# ver3_0_VinSeparat.net
KiCad netlist of a schematic drawn in EAGLE
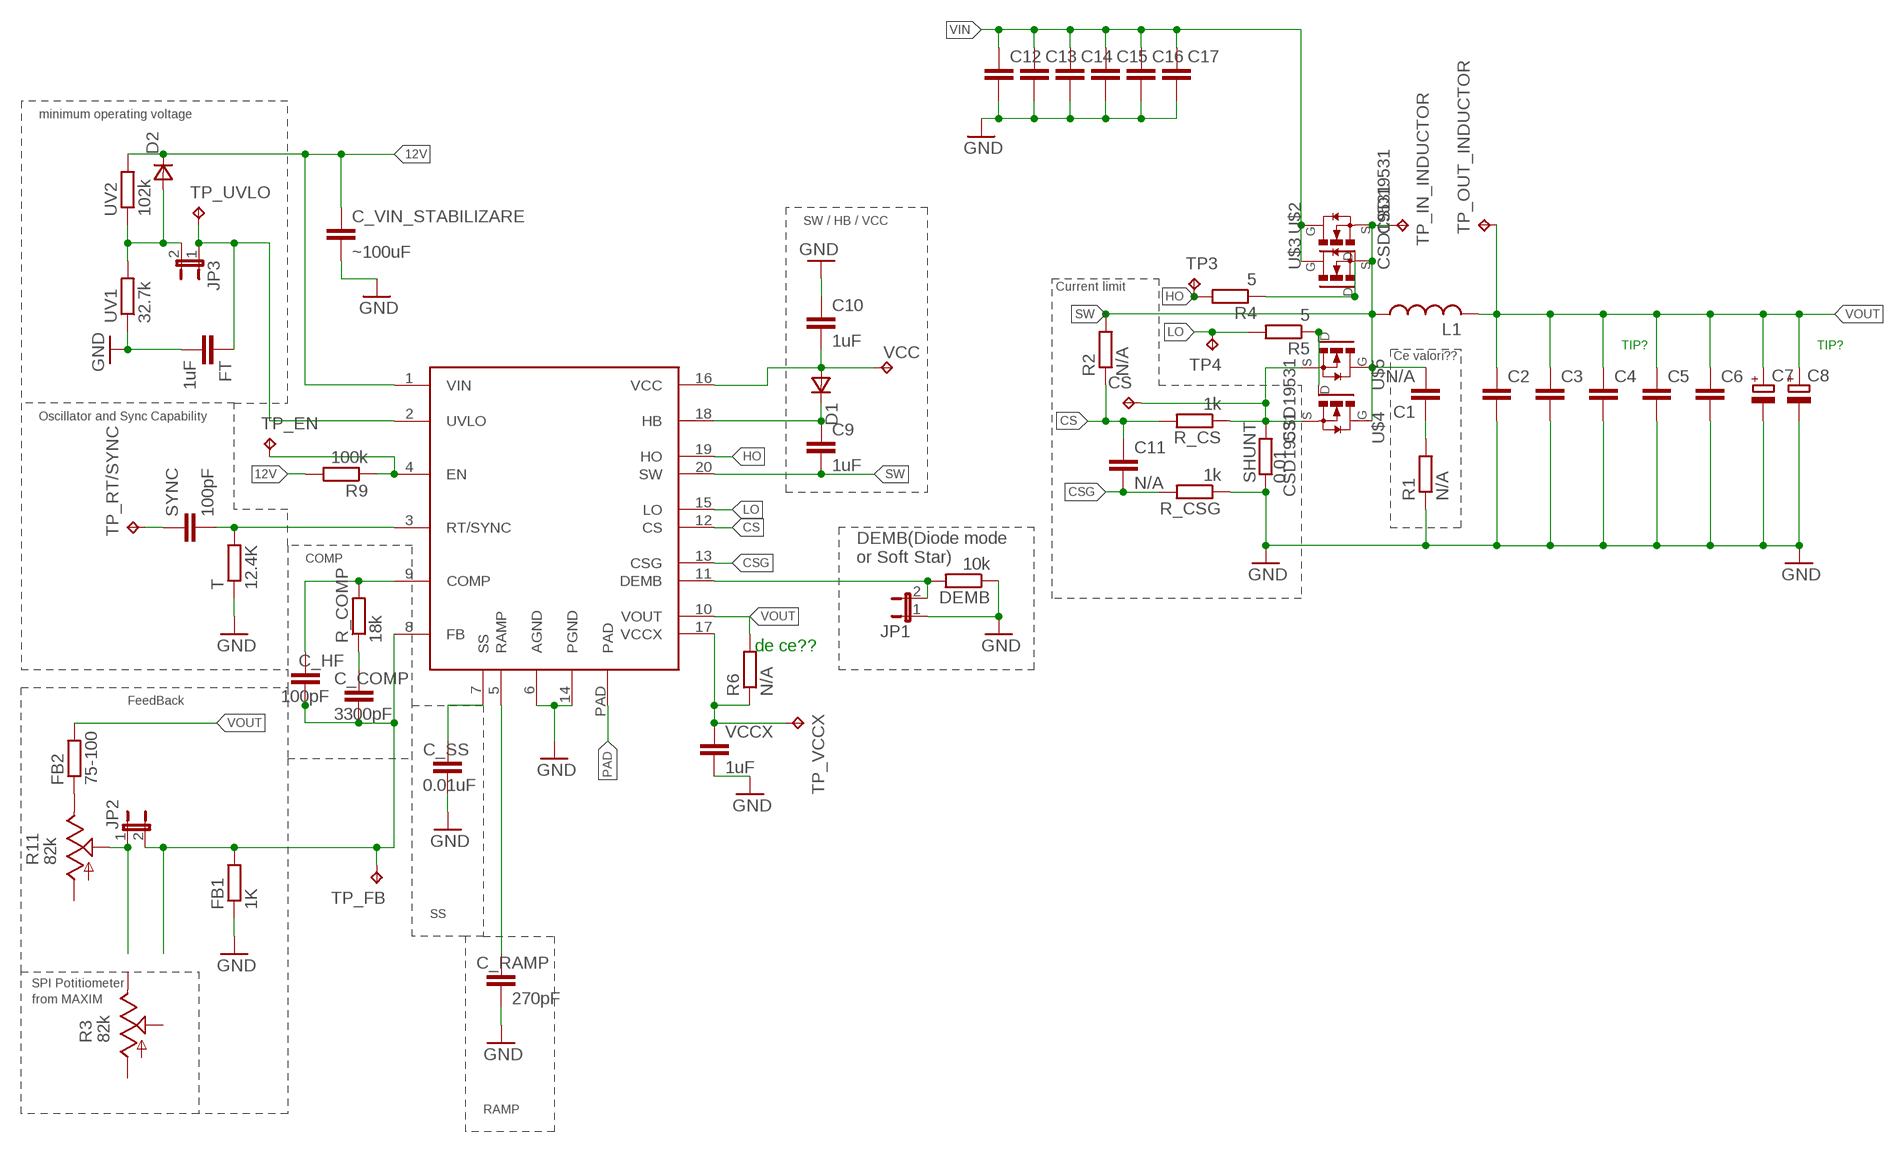
[diagram p0: schematic, sheet 1]

(export (version "E")
  (design (tool "Eeschema 10.0.6"))
  (components
    (comp (ref "C1")
      (value "N/A")
      (footprint "eagle-import:C0805K")
      (libsource (lib "eagle-import") (part "resistor_C-EUC0805K"))
    )
    (comp (ref "C2")
      (value "C-EUC1812")
      (footprint "eagle-import:C1812")
      (libsource (lib "eagle-import") (part "C-EUC1812"))
    )
    (comp (ref "C3")
      (value "C-EUC1812")
      (footprint "eagle-import:C1812")
      (libsource (lib "eagle-import") (part "C-EUC1812"))
    )
    (comp (ref "C4")
      (value "C-EUC1812")
      (footprint "eagle-import:C1812")
      (libsource (lib "eagle-import") (part "C-EUC1812"))
    )
    (comp (ref "C5")
      (value "C-EUC1812")
      (footprint "eagle-import:C1812")
      (libsource (lib "eagle-import") (part "C-EUC1812"))
    )
    (comp (ref "C6")
      (value "C-EUC1812")
      (footprint "eagle-import:C1812")
      (libsource (lib "eagle-import") (part "C-EUC1812"))
    )
    (comp (ref "C7")
      (value "CPOL-EU153CLV-1012")
      (footprint "eagle-import:153CLV-1012")
      (libsource (lib "eagle-import") (part "CPOL-EU153CLV-1012"))
    )
    (comp (ref "C8")
      (value "CPOL-EU153CLV-1012")
      (footprint "eagle-import:153CLV-1012")
      (libsource (lib "eagle-import") (part "CPOL-EU153CLV-1012"))
    )
    (comp (ref "C9")
      (value "1uF")
      (footprint "eagle-import:C0805K")
      (libsource (lib "eagle-import") (part "resistor_C-EUC0805K"))
    )
    (comp (ref "C10")
      (value "1uF")
      (footprint "eagle-import:C0805K")
      (libsource (lib "eagle-import") (part "resistor_C-EUC0805K"))
    )
    (comp (ref "C11")
      (value "N/A")
      (footprint "eagle-import:C0805K")
      (libsource (lib "eagle-import") (part "resistor_C-EUC0805K"))
    )
    (comp (ref "C12")
      (value "C-EUC1812K")
      (footprint "eagle-import:C1812K")
      (libsource (lib "eagle-import") (part "C-EUC1812K"))
    )
    (comp (ref "C13")
      (value "C-EUC1812K")
      (footprint "eagle-import:C1812K")
      (libsource (lib "eagle-import") (part "C-EUC1812K"))
    )
    (comp (ref "C14")
      (value "C-EUC1812K")
      (footprint "eagle-import:C1812K")
      (libsource (lib "eagle-import") (part "C-EUC1812K"))
    )
    (comp (ref "C15")
      (value "C-EUC1812K")
      (footprint "eagle-import:C1812K")
      (libsource (lib "eagle-import") (part "C-EUC1812K"))
    )
    (comp (ref "C16")
      (value "C-EUC1812K")
      (footprint "eagle-import:C1812K")
      (libsource (lib "eagle-import") (part "C-EUC1812K"))
    )
    (comp (ref "C17")
      (value "C-EUC1812K")
      (footprint "eagle-import:C1812K")
      (libsource (lib "eagle-import") (part "C-EUC1812K"))
    )
    (comp (ref "CS")
      (value "TPPAD1-20")
      (footprint "eagle-import:P1-20")
      (libsource (lib "eagle-import") (part "TPPAD1-20"))
    )
    (comp (ref "C_COMP")
      (value "3300pF")
      (footprint "eagle-import:C0805K")
      (libsource (lib "eagle-import") (part "resistor_C-EUC0805K"))
    )
    (comp (ref "C_HF")
      (value "100pF")
      (footprint "eagle-import:C0805K")
      (libsource (lib "eagle-import") (part "resistor_C-EUC0805K"))
    )
    (comp (ref "C_RAMP")
      (value "270pF")
      (footprint "eagle-import:C0805K")
      (libsource (lib "eagle-import") (part "resistor_C-EUC0805K"))
    )
    (comp (ref "C_SS")
      (value "0.01uF")
      (footprint "eagle-import:C0805K")
      (libsource (lib "eagle-import") (part "resistor_C-EUC0805K"))
    )
    (comp (ref "C_VIN_STABILIZARE")
      (value "~100uF")
      (footprint "eagle-import:C0805K")
      (libsource (lib "eagle-import") (part "resistor_C-EUC0805K"))
    )
    (comp (ref "D1")
      (value "DSOT23")
      (footprint "eagle-import:SOT-23")
      (fields (field (name "MPN") "CDSOT23-T03"))
      (libsource (lib "eagle-import") (part "DSOT23"))
    )
    (comp (ref "D2")
      (value "DSOT23")
      (footprint "eagle-import:SOT-23")
      (fields (field (name "MPN") "CDSOT23-T03"))
      (libsource (lib "eagle-import") (part "DSOT23"))
    )
    (comp (ref "DEMB")
      (value "10k")
      (footprint "eagle-import:R0603")
      (libsource (lib "eagle-import") (part "R-EU_R0603"))
    )
    (comp (ref "FB1")
      (value "1K")
      (footprint "eagle-import:R0603")
      (libsource (lib "eagle-import") (part "R-EU_R0603"))
    )
    (comp (ref "FB2")
      (value "75-100")
      (footprint "eagle-import:R0603")
      (libsource (lib "eagle-import") (part "R-EU_R0603"))
    )
    (comp (ref "FT")
      (value "1uF")
      (footprint "eagle-import:C1812K")
      (libsource (lib "eagle-import") (part "C-EUC1812K"))
    )
    (comp (ref "JP1")
      (value "JP1E")
      (footprint "eagle-import:JP1")
      (libsource (lib "eagle-import") (part "JP1E"))
    )
    (comp (ref "JP2")
      (value "JP1E")
      (footprint "eagle-import:JP1")
      (libsource (lib "eagle-import") (part "JP1E"))
    )
    (comp (ref "JP3")
      (value "JP1E")
      (footprint "eagle-import:JP1")
      (libsource (lib "eagle-import") (part "JP1E"))
    )
    (comp (ref "L1")
      (value "L-USTJ8-U2")
      (footprint "eagle-import:TJ8-U2")
      (libsource (lib "eagle-import") (part "L-USTJ8-U2"))
    )
    (comp (ref "R1")
      (value "N/A")
      (footprint "eagle-import:M1206")
      (libsource (lib "eagle-import") (part "resistor_R-EU_M1206"))
    )
    (comp (ref "R2")
      (value "N/A")
      (footprint "eagle-import:R0603")
      (libsource (lib "eagle-import") (part "R-EU_R0603"))
    )
    (comp (ref "R3")
      (value "82k")
      (footprint "eagle-import:B64Y")
      (libsource (lib "eagle-import") (part "TRIM_US-B64Y"))
    )
    (comp (ref "R4")
      (value "5")
      (footprint "eagle-import:M1206")
      (libsource (lib "eagle-import") (part "resistor_R-EU_M1206"))
    )
    (comp (ref "R5")
      (value "5")
      (footprint "eagle-import:M1206")
      (libsource (lib "eagle-import") (part "resistor_R-EU_M1206"))
    )
    (comp (ref "R6")
      (value "N/A")
      (footprint "eagle-import:R0603")
      (libsource (lib "eagle-import") (part "R-EU_R0603"))
    )
    (comp (ref "R9")
      (value "100k")
      (footprint "eagle-import:R0603")
      (libsource (lib "eagle-import") (part "R-EU_R0603"))
    )
    (comp (ref "R11")
      (value "82k")
      (footprint "eagle-import:B64Y")
      (libsource (lib "eagle-import") (part "TRIM_US-B64Y"))
    )
    (comp (ref "R_COMP")
      (value "18k")
      (footprint "eagle-import:R0603")
      (libsource (lib "eagle-import") (part "R-EU_R0603"))
    )
    (comp (ref "R_CS")
      (value "1k")
      (footprint "eagle-import:R0603")
      (libsource (lib "eagle-import") (part "R-EU_R0603"))
    )
    (comp (ref "R_CSG")
      (value "1k")
      (footprint "eagle-import:R0603")
      (libsource (lib "eagle-import") (part "R-EU_R0603"))
    )
    (comp (ref "SHUNT")
      (value "0.01")
      (footprint "eagle-import:SMR-0")
      (libsource (lib "eagle-import") (part "SMR-0"))
    )
    (comp (ref "SYNC")
      (value "100pF")
      (footprint "eagle-import:C0805K")
      (libsource (lib "eagle-import") (part "resistor_C-EUC0805K"))
    )
    (comp (ref "T")
      (value "12.4K")
      (footprint "eagle-import:R0603")
      (libsource (lib "eagle-import") (part "R-EU_R0603"))
    )
    (comp (ref "TP3")
      (value "TPPAD1-20")
      (footprint "eagle-import:P1-20")
      (libsource (lib "eagle-import") (part "TPPAD1-20"))
    )
    (comp (ref "TP4")
      (value "TPPAD1-20")
      (footprint "eagle-import:P1-20")
      (libsource (lib "eagle-import") (part "TPPAD1-20"))
    )
    (comp (ref "TP_EN")
      (value "TPPAD1-20")
      (footprint "eagle-import:P1-20")
      (libsource (lib "eagle-import") (part "TPPAD1-20"))
    )
    (comp (ref "TP_FB")
      (value "TPPAD1-20")
      (footprint "eagle-import:P1-20")
      (libsource (lib "eagle-import") (part "TPPAD1-20"))
    )
    (comp (ref "TP_IN_INDUCTOR")
      (value "TPPAD1-20")
      (footprint "eagle-import:P1-20")
      (libsource (lib "eagle-import") (part "TPPAD1-20"))
    )
    (comp (ref "TP_OUT_INDUCTOR")
      (value "TPPAD1-20")
      (footprint "eagle-import:P1-20")
      (libsource (lib "eagle-import") (part "TPPAD1-20"))
    )
    (comp (ref "TP_RT/SYNC")
      (value "TPPAD1-20")
      (footprint "eagle-import:P1-20")
      (libsource (lib "eagle-import") (part "TPPAD1-20"))
    )
    (comp (ref "TP_UVLO")
      (value "TPPAD1-20")
      (footprint "eagle-import:P1-20")
      (libsource (lib "eagle-import") (part "TPPAD1-20"))
    )
    (comp (ref "TP_VCCX")
      (value "TPPAD1-20")
      (footprint "eagle-import:P1-20")
      (libsource (lib "eagle-import") (part "TPPAD1-20"))
    )
    (comp (ref "U$1")
      (value "LM5116")
      (footprint "eagle-import:TSSOP20")
      (libsource (lib "eagle-import") (part "LM5116"))
    )
    (comp (ref "U$2")
      (value "CSD19531")
      (footprint "eagle-import:TO220H")
      (libsource (lib "eagle-import") (part "CSD19531"))
    )
    (comp (ref "U$3")
      (value "CSD19531")
      (footprint "eagle-import:TO220H")
      (libsource (lib "eagle-import") (part "CSD19531"))
    )
    (comp (ref "U$4")
      (value "CSD19531")
      (footprint "eagle-import:TO220H")
      (libsource (lib "eagle-import") (part "CSD19531"))
    )
    (comp (ref "U$5")
      (value "CSD19531")
      (footprint "eagle-import:TO220H")
      (libsource (lib "eagle-import") (part "CSD19531"))
    )
    (comp (ref "UV1")
      (value "32.7k")
      (footprint "eagle-import:R0603")
      (libsource (lib "eagle-import") (part "R-EU_R0603"))
    )
    (comp (ref "UV2")
      (value "102k")
      (footprint "eagle-import:R0603")
      (libsource (lib "eagle-import") (part "R-EU_R0603"))
    )
    (comp (ref "VCC")
      (value "TPPAD1-20")
      (footprint "eagle-import:P1-20")
      (libsource (lib "eagle-import") (part "TPPAD1-20"))
    )
    (comp (ref "VCCX")
      (value "1uF")
      (footprint "eagle-import:C0805K")
      (libsource (lib "eagle-import") (part "resistor_C-EUC0805K"))
    )
  )
  (nets
    (net (code "1") (name "12V") (class "Default")
      (node (ref "C_VIN_STABILIZARE") (pin "1") (pinfunction "1_1") (pintype "passive"))
      (node (ref "D2") (pin "1") (pinfunction "C_1") (pintype "passive"))
      (node (ref "R9") (pin "2") (pinfunction "2_2") (pintype "passive"))
      (node (ref "U$1") (pin "1") (pinfunction "VIN_1") (pintype "power_in"))
      (node (ref "UV2") (pin "2") (pinfunction "2_2") (pintype "passive"))
    )
    (net (code "2") (name "CS") (class "Default")
      (node (ref "C11") (pin "1") (pinfunction "1_1") (pintype "passive"))
      (node (ref "R2") (pin "1") (pinfunction "1_1") (pintype "passive"))
      (node (ref "R_CS") (pin "2") (pinfunction "2_2") (pintype "passive"))
      (node (ref "U$1") (pin "12") (pinfunction "CS_12") (pintype "bidirectional"))
    )
    (net (code "3") (name "CSG") (class "Default")
      (node (ref "C11") (pin "2") (pinfunction "2_2") (pintype "passive"))
      (node (ref "R_CSG") (pin "2") (pinfunction "2_2") (pintype "passive"))
      (node (ref "U$1") (pin "13") (pinfunction "CSG_13") (pintype "bidirectional"))
    )
    (net (code "4") (name "GND") (class "Default")
      (node (ref "C10") (pin "1") (pinfunction "1_1") (pintype "passive"))
      (node (ref "C12") (pin "2") (pinfunction "2_2") (pintype "passive"))
      (node (ref "C13") (pin "2") (pinfunction "2_2") (pintype "passive"))
      (node (ref "C14") (pin "2") (pinfunction "2_2") (pintype "passive"))
      (node (ref "C15") (pin "2") (pinfunction "2_2") (pintype "passive"))
      (node (ref "C16") (pin "2") (pinfunction "2_2") (pintype "passive"))
      (node (ref "C17") (pin "2") (pinfunction "2_2") (pintype "passive"))
      (node (ref "C2") (pin "2") (pinfunction "2_2") (pintype "passive"))
      (node (ref "C3") (pin "2") (pinfunction "2_2") (pintype "passive"))
      (node (ref "C4") (pin "2") (pinfunction "2_2") (pintype "passive"))
      (node (ref "C5") (pin "2") (pinfunction "2_2") (pintype "passive"))
      (node (ref "C6") (pin "2") (pinfunction "2_2") (pintype "passive"))
      (node (ref "C7") (pin "-") (pinfunction "-_-") (pintype "passive"))
      (node (ref "C8") (pin "-") (pinfunction "-_-") (pintype "passive"))
      (node (ref "C_RAMP") (pin "2") (pinfunction "2_2") (pintype "passive"))
      (node (ref "C_SS") (pin "2") (pinfunction "2_2") (pintype "passive"))
      (node (ref "C_VIN_STABILIZARE") (pin "2") (pinfunction "2_2") (pintype "passive"))
      (node (ref "DEMB") (pin "1") (pinfunction "1_1") (pintype "passive"))
      (node (ref "FB1") (pin "1") (pinfunction "1_1") (pintype "passive"))
      (node (ref "FT") (pin "2") (pinfunction "2_2") (pintype "passive"))
      (node (ref "JP1") (pin "1") (pinfunction "1_1") (pintype "passive"))
      (node (ref "R1") (pin "1") (pinfunction "1_1") (pintype "passive"))
      (node (ref "R_CSG") (pin "1") (pinfunction "1_1") (pintype "passive"))
      (node (ref "SHUNT") (pin "2") (pinfunction "2_2") (pintype "passive"))
      (node (ref "T") (pin "1") (pinfunction "1_1") (pintype "passive"))
      (node (ref "U$1") (pin "14") (pinfunction "PGND_14") (pintype "bidirectional"))
      (node (ref "U$1") (pin "6") (pinfunction "AGND_6") (pintype "bidirectional"))
      (node (ref "UV1") (pin "1") (pinfunction "1_1") (pintype "passive"))
      (node (ref "VCCX") (pin "2") (pinfunction "2_2") (pintype "passive"))
    )
    (net (code "5") (name "HO") (class "Default")
      (node (ref "R4") (pin "2") (pinfunction "2_2") (pintype "passive"))
      (node (ref "TP3") (pin "TP") (pinfunction "TP_TP") (pintype "input"))
      (node (ref "U$1") (pin "19") (pinfunction "HO_19") (pintype "bidirectional"))
    )
    (net (code "6") (name "LO") (class "Default")
      (node (ref "R5") (pin "2") (pinfunction "2_2") (pintype "passive"))
      (node (ref "TP4") (pin "TP") (pinfunction "TP_TP") (pintype "input"))
      (node (ref "U$1") (pin "15") (pinfunction "LO_15") (pintype "bidirectional"))
    )
    (net (code "7") (name "Net-(C1-Pad1)") (class "Default")
      (node (ref "C1") (pin "1") (pinfunction "1_1") (pintype "passive"))
      (node (ref "R1") (pin "2") (pinfunction "2_2") (pintype "passive"))
    )
    (net (code "8") (name "Net-(C_COMP-Pad1)") (class "Default")
      (node (ref "C_COMP") (pin "1") (pinfunction "1_1") (pintype "passive"))
      (node (ref "R_COMP") (pin "1") (pinfunction "1_1") (pintype "passive"))
    )
    (net (code "9") (name "Net-(D1-A)") (class "Default")
      (node (ref "C10") (pin "2") (pinfunction "2_2") (pintype "passive"))
      (node (ref "D1") (pin "3") (pinfunction "A_3") (pintype "passive"))
      (node (ref "U$1") (pin "16") (pinfunction "VCC_16") (pintype "bidirectional"))
      (node (ref "VCC") (pin "TP") (pinfunction "TP_TP") (pintype "input"))
    )
    (net (code "10") (name "Net-(D1-C)") (class "Default")
      (node (ref "C9") (pin "1") (pinfunction "1_1") (pintype "passive"))
      (node (ref "D1") (pin "1") (pinfunction "C_1") (pintype "passive"))
      (node (ref "U$1") (pin "18") (pinfunction "HB_18") (pintype "bidirectional"))
    )
    (net (code "11") (name "Net-(D2-A)") (class "Default")
      (node (ref "D2") (pin "3") (pinfunction "A_3") (pintype "passive"))
      (node (ref "JP3") (pin "2") (pinfunction "2_2") (pintype "passive"))
      (node (ref "UV1") (pin "2") (pinfunction "2_2") (pintype "passive"))
      (node (ref "UV2") (pin "1") (pinfunction "1_1") (pintype "passive"))
    )
    (net (code "12") (name "Net-(FB2-Pad1)") (class "Default")
      (node (ref "FB2") (pin "1") (pinfunction "1_1") (pintype "passive"))
      (node (ref "R11") (pin "E") (pinfunction "E_E") (pintype "passive"))
    )
    (net (code "13") (name "Net-(JP2-Pad1)") (class "Default")
      (node (ref "JP2") (pin "1") (pinfunction "1_1") (pintype "passive"))
      (node (ref "R11") (pin "S") (pinfunction "S_S") (pintype "passive"))
    )
    (net (code "14") (name "Net-(SYNC-Pad1)") (class "Default")
      (node (ref "SYNC") (pin "1") (pinfunction "1_1") (pintype "passive"))
      (node (ref "TP_RT/SYNC") (pin "TP") (pinfunction "TP_TP") (pintype "input"))
    )
    (net (code "15") (name "Net-(U$1-COMP)") (class "Default")
      (node (ref "C_HF") (pin "1") (pinfunction "1_1") (pintype "passive"))
      (node (ref "R_COMP") (pin "2") (pinfunction "2_2") (pintype "passive"))
      (node (ref "U$1") (pin "9") (pinfunction "COMP_9") (pintype "bidirectional"))
    )
    (net (code "16") (name "Net-(U$1-DEMB)") (class "Default")
      (node (ref "DEMB") (pin "2") (pinfunction "2_2") (pintype "passive"))
      (node (ref "JP1") (pin "2") (pinfunction "2_2") (pintype "passive"))
      (node (ref "U$1") (pin "11") (pinfunction "DEMB_11") (pintype "bidirectional"))
    )
    (net (code "17") (name "Net-(U$1-EN)") (class "Default")
      (node (ref "R9") (pin "1") (pinfunction "1_1") (pintype "passive"))
      (node (ref "TP_EN") (pin "TP") (pinfunction "TP_TP") (pintype "input"))
      (node (ref "U$1") (pin "4") (pinfunction "EN_4") (pintype "bidirectional"))
    )
    (net (code "18") (name "Net-(U$1-FB)") (class "Default")
      (node (ref "C_COMP") (pin "2") (pinfunction "2_2") (pintype "passive"))
      (node (ref "C_HF") (pin "2") (pinfunction "2_2") (pintype "passive"))
      (node (ref "FB1") (pin "2") (pinfunction "2_2") (pintype "passive"))
      (node (ref "JP2") (pin "2") (pinfunction "2_2") (pintype "passive"))
      (node (ref "TP_FB") (pin "TP") (pinfunction "TP_TP") (pintype "input"))
      (node (ref "U$1") (pin "8") (pinfunction "FB_8") (pintype "bidirectional"))
    )
    (net (code "19") (name "Net-(U$1-RAMP)") (class "Default")
      (node (ref "C_RAMP") (pin "1") (pinfunction "1_1") (pintype "passive"))
      (node (ref "U$1") (pin "5") (pinfunction "RAMP_5") (pintype "bidirectional"))
    )
    (net (code "20") (name "Net-(U$1-RT{slash}SYNC)") (class "Default")
      (node (ref "SYNC") (pin "2") (pinfunction "2_2") (pintype "passive"))
      (node (ref "T") (pin "2") (pinfunction "2_2") (pintype "passive"))
      (node (ref "U$1") (pin "3") (pinfunction "RT/SYNC_3") (pintype "bidirectional"))
    )
    (net (code "21") (name "Net-(U$1-SS)") (class "Default")
      (node (ref "C_SS") (pin "1") (pinfunction "1_1") (pintype "passive"))
      (node (ref "U$1") (pin "7") (pinfunction "SS_7") (pintype "bidirectional"))
    )
    (net (code "22") (name "Net-(U$1-UVLO)") (class "Default")
      (node (ref "FT") (pin "1") (pinfunction "1_1") (pintype "passive"))
      (node (ref "JP3") (pin "1") (pinfunction "1_1") (pintype "passive"))
      (node (ref "TP_UVLO") (pin "TP") (pinfunction "TP_TP") (pintype "input"))
      (node (ref "U$1") (pin "2") (pinfunction "UVLO_2") (pintype "bidirectional"))
    )
    (net (code "23") (name "Net-(U$1-VCCX)") (class "Default")
      (node (ref "R6") (pin "1") (pinfunction "1_1") (pintype "passive"))
      (node (ref "TP_VCCX") (pin "TP") (pinfunction "TP_TP") (pintype "input"))
      (node (ref "U$1") (pin "17") (pinfunction "VCCX_17") (pintype "bidirectional"))
      (node (ref "VCCX") (pin "1") (pinfunction "1_1") (pintype "passive"))
    )
    (net (code "24") (name "Net-(U$2-G)") (class "Default")
      (node (ref "R4") (pin "1") (pinfunction "1_1") (pintype "passive"))
      (node (ref "U$2") (pin "1") (pinfunction "G_1") (pintype "passive"))
      (node (ref "U$3") (pin "1") (pinfunction "G_1") (pintype "passive"))
    )
    (net (code "25") (name "Net-(U$4-G)") (class "Default")
      (node (ref "R5") (pin "1") (pinfunction "1_1") (pintype "passive"))
      (node (ref "U$4") (pin "1") (pinfunction "G_1") (pintype "passive"))
      (node (ref "U$5") (pin "1") (pinfunction "G_1") (pintype "passive"))
    )
    (net (code "26") (name "Net-(U$4-S)") (class "Default")
      (node (ref "CS") (pin "TP") (pinfunction "TP_TP") (pintype "input"))
      (node (ref "R_CS") (pin "1") (pinfunction "1_1") (pintype "passive"))
      (node (ref "SHUNT") (pin "1") (pinfunction "1_1") (pintype "passive"))
      (node (ref "U$4") (pin "3") (pinfunction "S_3") (pintype "passive"))
      (node (ref "U$5") (pin "3") (pinfunction "S_3") (pintype "passive"))
    )
    (net (code "27") (name "PAD") (class "Default")
      (node (ref "U$1") (pin "PAD") (pinfunction "PAD_PAD") (pintype "bidirectional"))
    )
    (net (code "28") (name "SW") (class "Default")
      (node (ref "C1") (pin "2") (pinfunction "2_2") (pintype "passive"))
      (node (ref "C9") (pin "2") (pinfunction "2_2") (pintype "passive"))
      (node (ref "L1") (pin "1") (pinfunction "1_1") (pintype "passive"))
      (node (ref "R2") (pin "2") (pinfunction "2_2") (pintype "passive"))
      (node (ref "TP_IN_INDUCTOR") (pin "TP") (pinfunction "TP_TP") (pintype "input"))
      (node (ref "U$1") (pin "20") (pinfunction "SW_20") (pintype "bidirectional"))
      (node (ref "U$2") (pin "3") (pinfunction "S_3") (pintype "passive"))
      (node (ref "U$3") (pin "3") (pinfunction "S_3") (pintype "passive"))
      (node (ref "U$4") (pin "2") (pinfunction "D_2") (pintype "passive"))
      (node (ref "U$4") (pin "T") (pinfunction "D_T") (pintype "passive"))
      (node (ref "U$5") (pin "2") (pinfunction "D_2") (pintype "passive"))
      (node (ref "U$5") (pin "T") (pinfunction "D_T") (pintype "passive"))
    )
    (net (code "29") (name "VIN") (class "Default")
      (node (ref "C12") (pin "1") (pinfunction "1_1") (pintype "passive"))
      (node (ref "C13") (pin "1") (pinfunction "1_1") (pintype "passive"))
      (node (ref "C14") (pin "1") (pinfunction "1_1") (pintype "passive"))
      (node (ref "C15") (pin "1") (pinfunction "1_1") (pintype "passive"))
      (node (ref "C16") (pin "1") (pinfunction "1_1") (pintype "passive"))
      (node (ref "C17") (pin "1") (pinfunction "1_1") (pintype "passive"))
      (node (ref "U$2") (pin "2") (pinfunction "D_2") (pintype "passive"))
      (node (ref "U$2") (pin "T") (pinfunction "D_T") (pintype "passive"))
      (node (ref "U$3") (pin "2") (pinfunction "D_2") (pintype "passive"))
      (node (ref "U$3") (pin "T") (pinfunction "D_T") (pintype "passive"))
    )
    (net (code "30") (name "VOUT") (class "Default")
      (node (ref "C2") (pin "1") (pinfunction "1_1") (pintype "passive"))
      (node (ref "C3") (pin "1") (pinfunction "1_1") (pintype "passive"))
      (node (ref "C4") (pin "1") (pinfunction "1_1") (pintype "passive"))
      (node (ref "C5") (pin "1") (pinfunction "1_1") (pintype "passive"))
      (node (ref "C6") (pin "1") (pinfunction "1_1") (pintype "passive"))
      (node (ref "C7") (pin "+") (pinfunction "+_+") (pintype "passive"))
      (node (ref "C8") (pin "+") (pinfunction "+_+") (pintype "passive"))
      (node (ref "FB2") (pin "2") (pinfunction "2_2") (pintype "passive"))
      (node (ref "L1") (pin "2") (pinfunction "2_2") (pintype "passive"))
      (node (ref "R6") (pin "2") (pinfunction "2_2") (pintype "passive"))
      (node (ref "TP_OUT_INDUCTOR") (pin "TP") (pinfunction "TP_TP") (pintype "input"))
      (node (ref "U$1") (pin "10") (pinfunction "VOUT_10") (pintype "bidirectional"))
    )
    (net (code "31") (name "unconnected-(R3-PadA)") (class "Default")
      (node (ref "R3") (pin "A") (pinfunction "A_A") (pintype "passive"))
    )
    (net (code "32") (name "unconnected-(R3-PadE)") (class "Default")
      (node (ref "R3") (pin "E") (pinfunction "E_E") (pintype "passive"))
    )
    (net (code "33") (name "unconnected-(R3-PadS)") (class "Default")
      (node (ref "R3") (pin "S") (pinfunction "S_S") (pintype "passive"))
    )
    (net (code "34") (name "unconnected-(R11-PadA)") (class "Default")
      (node (ref "R11") (pin "A") (pinfunction "A_A") (pintype "passive"))
    )
  )
)
